# SCH_ZX-WiFi_2025-05-12.net
KiCad netlist of a schematic drawn in EasyEDA
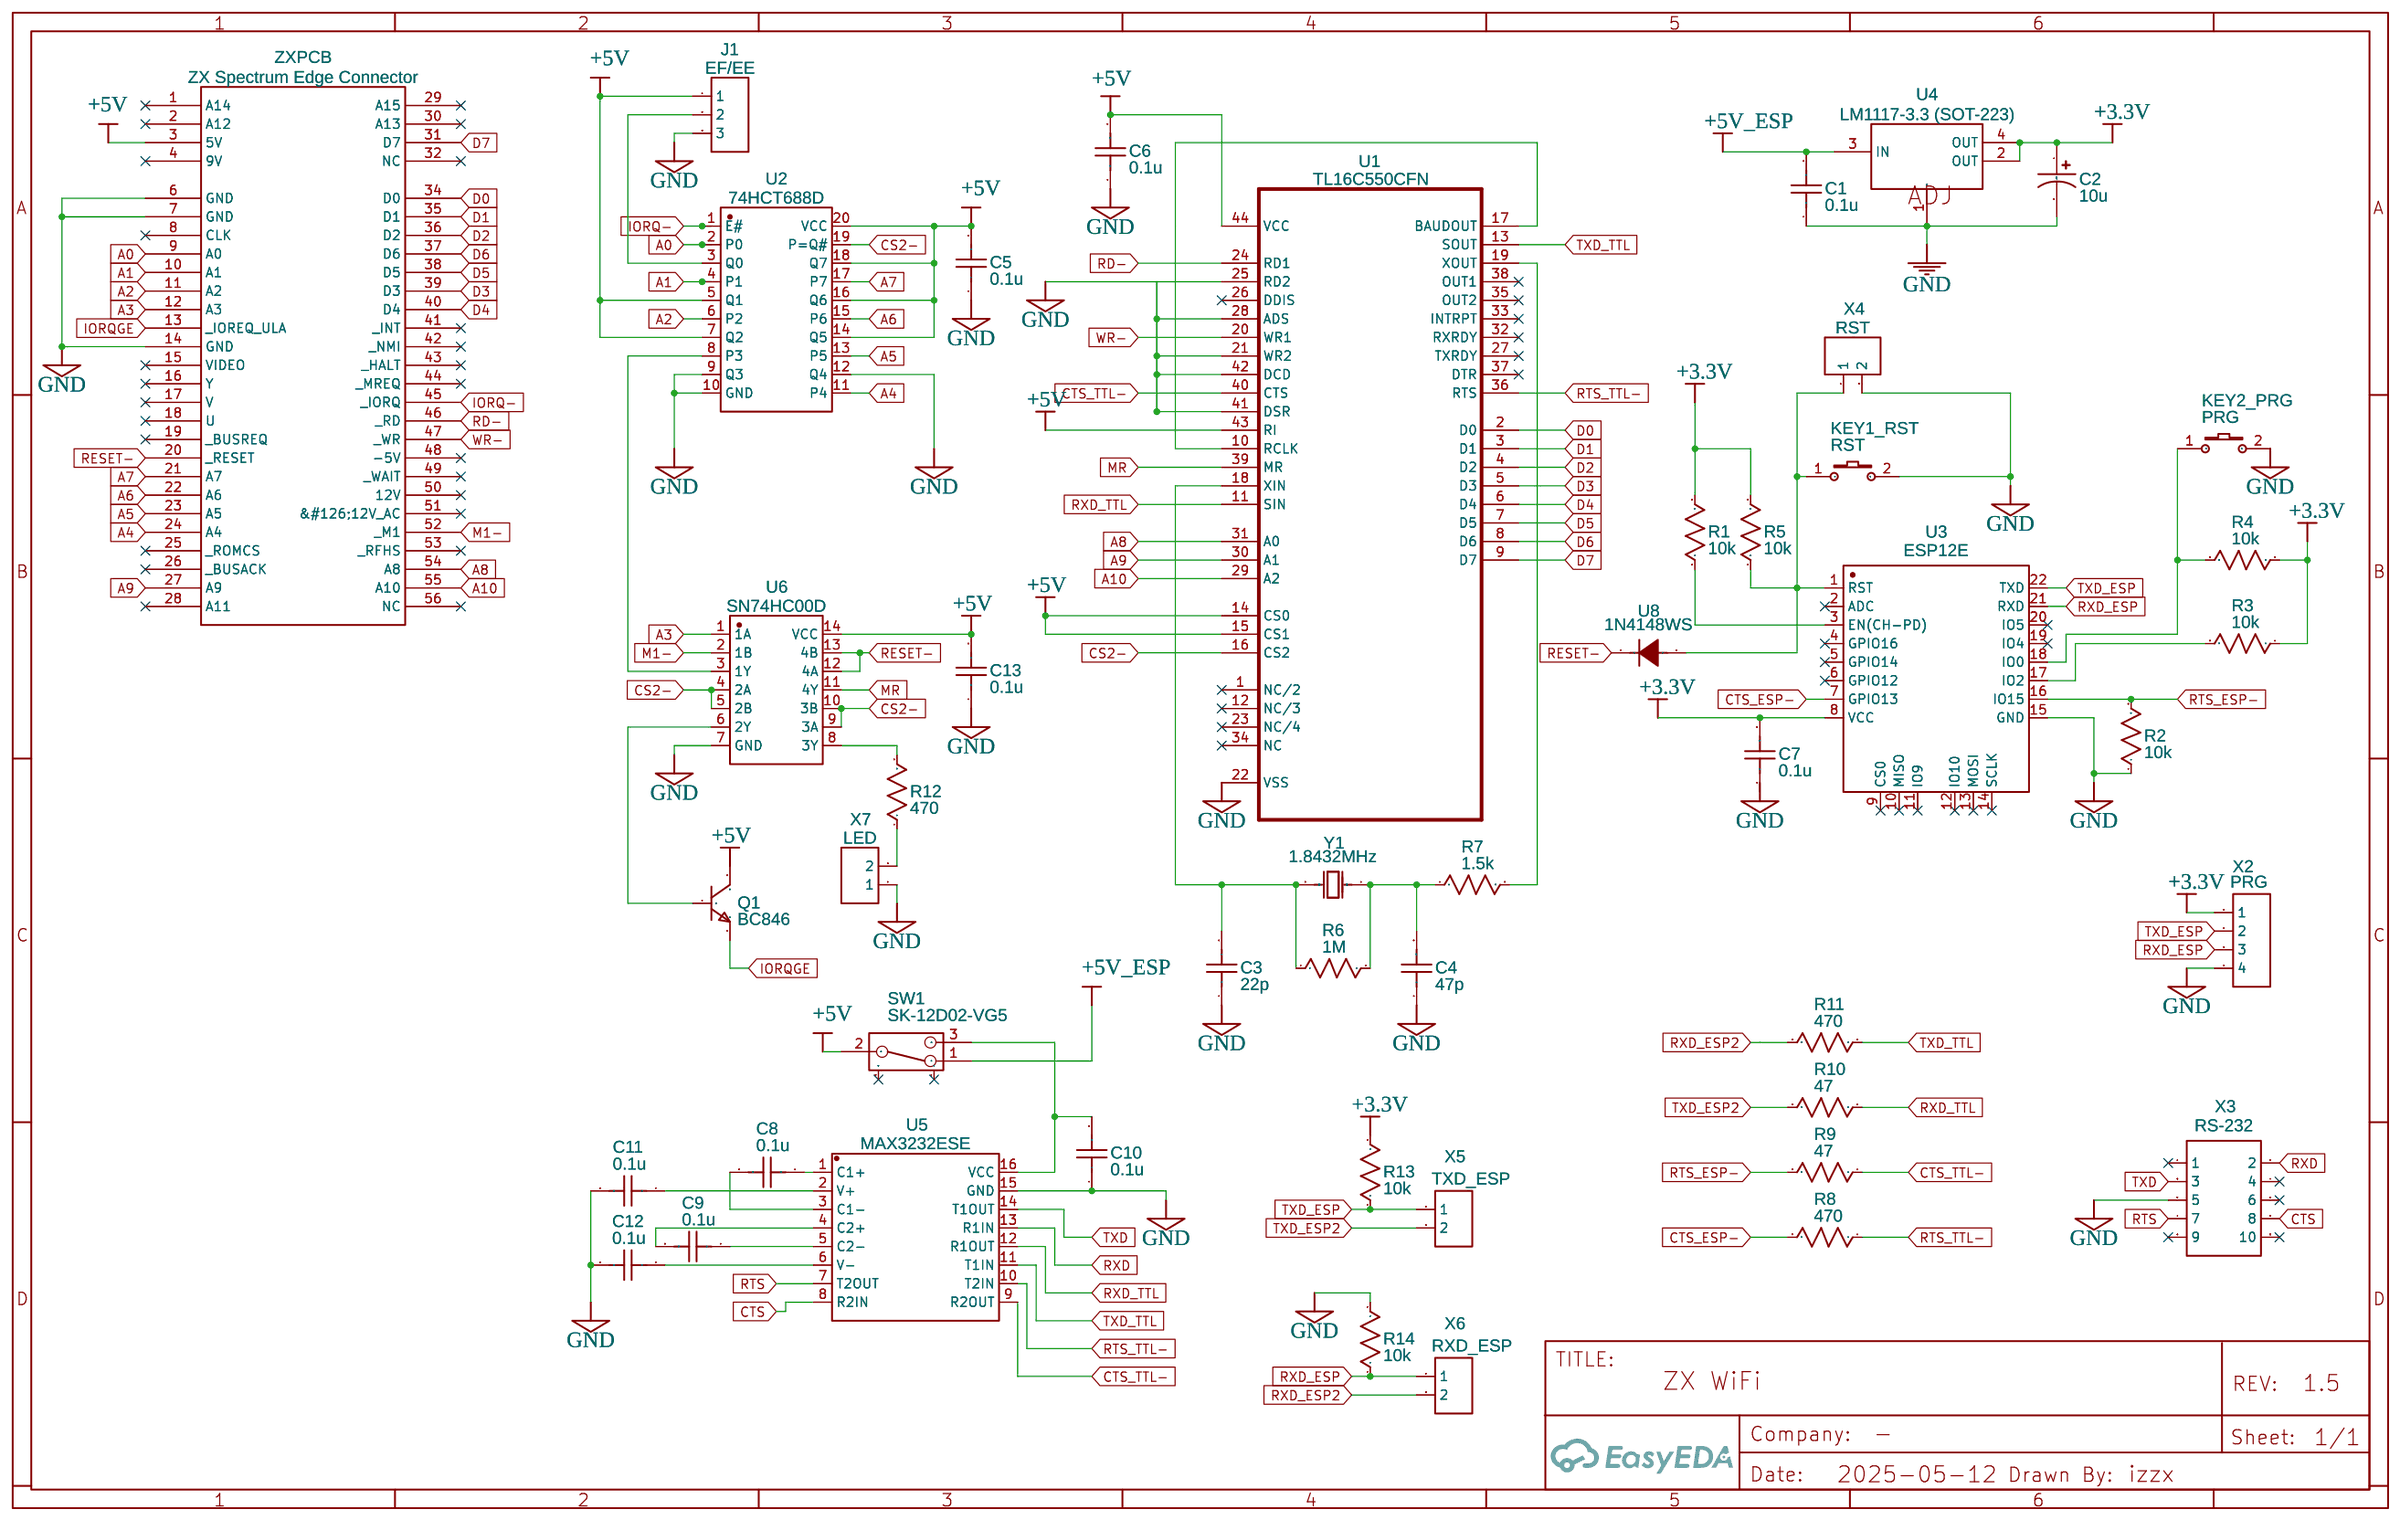
[diagram p0: schematic sheet]

(export (version "E")
  (design (tool "Eeschema 10.0.6"))
  (components
    (comp (ref "C1") (value "0.1u") (libsource (lib "") (part "C_0805_US")))
    (comp (ref "C2") (value "10u") (libsource (lib "") (part "C_Tan_SMD_A_US")))
    (comp (ref "C3") (value "22p") (libsource (lib "") (part "C_0805_US")))
    (comp (ref "C4") (value "47p") (libsource (lib "") (part "C_0805_US")))
    (comp (ref "C5") (value "0.1u") (libsource (lib "") (part "C_0805_US")))
    (comp (ref "C6") (value "0.1u") (libsource (lib "") (part "C_0805_US")))
    (comp (ref "C7") (value "0.1u") (libsource (lib "") (part "C_0805_US")))
    (comp (ref "C8") (value "0.1u") (libsource (lib "") (part "C_0805_US_1")))
    (comp (ref "C9") (value "0.1u") (libsource (lib "") (part "C_0805_US_1")))
    (comp (ref "C10") (value "0.1u") (libsource (lib "") (part "C_0805_US")))
    (comp (ref "C11") (value "0.1u") (libsource (lib "") (part "C_0805_US_1")))
    (comp (ref "C12") (value "0.1u") (libsource (lib "") (part "C_0805_US_1")))
    (comp (ref "C13") (value "0.1u") (libsource (lib "") (part "C_0805_US")))
    (comp (ref "J1") (value "EF/EE") (libsource (lib "") (part "HDR-M-2.54_1x3")))
    (comp (ref "KEY1_RST")
      (value "RST")
      (fields (field (name "Manufacturer Part") "K2-1107ST-A4SW-06"))
      (libsource (lib "") (part "K2-3.6×6.1_SMD"))
    )
    (comp (ref "KEY2_PRG")
      (value "PRG")
      (fields (field (name "Manufacturer Part") "K2-1107ST-A4SW-06"))
      (libsource (lib "") (part "K2-3.6×6.1_SMD_1"))
    )
    (comp (ref "Q1")
      (value "BC846")
      (fields (field (name "Manufacturer Part") "BC846A") (field (name "Manufacturer") "CJ(江苏长电/长晶)"))
      (libsource (lib "") (part "BC846"))
    )
    (comp (ref "R1") (value "10k") (libsource (lib "") (part "R_0805_US_1")))
    (comp (ref "R2") (value "10k") (libsource (lib "") (part "R_0805_US_1")))
    (comp (ref "R3") (value "10k") (libsource (lib "") (part "R_0805_US")))
    (comp (ref "R4") (value "10k") (libsource (lib "") (part "R_0805_US")))
    (comp (ref "R5") (value "10k") (libsource (lib "") (part "R_0805_US_1")))
    (comp (ref "R6") (value "1M") (libsource (lib "") (part "R_0805_US_2")))
    (comp (ref "R7") (value "1.5k") (libsource (lib "") (part "R_0805_US_2")))
    (comp (ref "R8") (value "470") (libsource (lib "") (part "R_0805_US")))
    (comp (ref "R9") (value "47") (libsource (lib "") (part "R_0805_US")))
    (comp (ref "R10") (value "47") (libsource (lib "") (part "R_0805_US")))
    (comp (ref "R11") (value "470") (libsource (lib "") (part "R_0805_US")))
    (comp (ref "R12") (value "470") (libsource (lib "") (part "R_0805_US_1")))
    (comp (ref "R13") (value "10k") (libsource (lib "") (part "R_0805_US_1")))
    (comp (ref "R14") (value "10k") (libsource (lib "") (part "R_0805_US_1")))
    (comp (ref "SW1")
      (value "SK-12D02-VG5")
      (fields (field (name "Manufacturer") "Rectangular Connectors - Contacts"))
      (libsource (lib "") (part "SK-12D02-VG5"))
    )
    (comp (ref "U1") (value "TL16C550CFN") (libsource (lib "") (part "TL16C550CFN")))
    (comp (ref "U2")
      (value "74HCT688D")
      (fields (field (name "Manufacturer") "PHILIPS"))
      (libsource (lib "") (part "74HCT688D"))
    )
    (comp (ref "U3") (value "ESP12E") (libsource (lib "") (part "ESP12E/F")))
    (comp (ref "U4")
      (value "LM1117-3.3 (SOT-223)")
      (fields (field (name "Manufacturer Part") "LM317G-AA3-R") (field (name "Manufacturer") "UTC"))
      (libsource (lib "") (part "LM317(SOT-223)"))
    )
    (comp (ref "U5")
      (value "MAX3232ESE")
      (fields (field (name "Manufacturer") "UMW(友台半导体)"))
      (libsource (lib "") (part "MAX3232ESE"))
    )
    (comp (ref "U6")
      (value "SN74HC00D")
      (fields (field (name "Manufacturer") "TI(德州仪器)"))
      (libsource (lib "") (part "SN74HC00D"))
    )
    (comp (ref "U8")
      (value "1N4148WS")
      (fields (field (name "Manufacturer") "Zhengxin(正芯)"))
      (libsource (lib "") (part "1N4148WS"))
    )
    (comp (ref "X2") (value "PRG") (libsource (lib "") (part "HDR-M-2.54_1x4")))
    (comp (ref "X3") (value "RS-232") (libsource (lib "") (part "HDR-M-2.54_2x5")))
    (comp (ref "X4") (value "RST") (libsource (lib "") (part "HDR-M-2.54_1x2")))
    (comp (ref "X5") (value "TXD_ESP") (libsource (lib "") (part "HDR-F-2.54_1x2")))
    (comp (ref "X6") (value "RXD_ESP") (libsource (lib "") (part "HDR-F-2.54_1x2")))
    (comp (ref "X7") (value "LED") (libsource (lib "") (part "HDR-M-2.54_1x2_1")))
    (comp (ref "Y1")
      (value "1.8432MHz")
      (fields (field (name "Manufacturer Part") "X49UD3579MSD2SC") (field (name "Manufacturer") "ValuePro"))
      (libsource (lib "") (part "X49UD3579MSD2SC"))
    )
    (comp (ref "ZXPCB")
      (value "ZX Spectrum Edge Connector")
      (libsource (lib "") (part "ZX Spectrum Edge Connector"))
    )
  )
  (nets
    (net (code "1") (name "+3.3V") (class "Default")
      (node (ref "C2") (pin "1") (pinfunction "1_1") (pintype "unspecified"))
      (node (ref "C7") (pin "2") (pinfunction "2_2") (pintype "unspecified"))
      (node (ref "R1") (pin "2") (pinfunction "2_2") (pintype "unspecified"))
      (node (ref "R13") (pin "2") (pinfunction "2_2") (pintype "unspecified"))
      (node (ref "R3") (pin "1") (pinfunction "1_1") (pintype "unspecified"))
      (node (ref "R4") (pin "1") (pinfunction "1_1") (pintype "unspecified"))
      (node (ref "R5") (pin "2") (pinfunction "2_2") (pintype "unspecified"))
      (node (ref "U3") (pin "8") (pinfunction "VCC_8") (pintype "unspecified"))
      (node (ref "U4") (pin "2") (pinfunction "OUT_2") (pintype "passive"))
      (node (ref "U4") (pin "4") (pinfunction "OUT_4") (pintype "passive"))
      (node (ref "X2") (pin "1") (pinfunction "1_1") (pintype "unspecified"))
    )
    (net (code "2") (name "+5V") (class "Default")
      (node (ref "C13") (pin "2") (pinfunction "2_2") (pintype "unspecified"))
      (node (ref "C5") (pin "2") (pinfunction "2_2") (pintype "unspecified"))
      (node (ref "C6") (pin "2") (pinfunction "2_2") (pintype "unspecified"))
      (node (ref "J1") (pin "1") (pinfunction "1_1") (pintype "input"))
      (node (ref "Q1") (pin "3") (pinfunction "C_3") (pintype "unspecified"))
      (node (ref "SW1") (pin "2") (pinfunction "2_2") (pintype "unspecified"))
      (node (ref "U1") (pin "14") (pinfunction "CS0_14") (pintype "input"))
      (node (ref "U1") (pin "15") (pinfunction "CS1_15") (pintype "input"))
      (node (ref "U1") (pin "43") (pinfunction "RI_43") (pintype "input"))
      (node (ref "U1") (pin "44") (pinfunction "VCC_44") (pintype "passive"))
      (node (ref "U2") (pin "14") (pinfunction "Q5_14") (pintype "unspecified"))
      (node (ref "U2") (pin "16") (pinfunction "Q6_16") (pintype "unspecified"))
      (node (ref "U2") (pin "18") (pinfunction "Q7_18") (pintype "unspecified"))
      (node (ref "U2") (pin "20") (pinfunction "VCC_20") (pintype "unspecified"))
      (node (ref "U2") (pin "5") (pinfunction "Q1_5") (pintype "unspecified"))
      (node (ref "U2") (pin "7") (pinfunction "Q2_7") (pintype "unspecified"))
      (node (ref "U6") (pin "14") (pinfunction "VCC_14") (pintype "unspecified"))
      (node (ref "ZXPCB") (pin "3") (pinfunction "5V_3") (pintype "unspecified"))
    )
    (net (code "3") (name "+5V_ESP") (class "Default")
      (node (ref "C1") (pin "2") (pinfunction "2_2") (pintype "unspecified"))
      (node (ref "SW1") (pin "1") (pinfunction "1_1") (pintype "unspecified"))
      (node (ref "U4") (pin "3") (pinfunction "IN_3") (pintype "passive"))
    )
    (net (code "4") (name "A0") (class "Default")
      (node (ref "U2") (pin "2") (pinfunction "P0_2") (pintype "unspecified"))
      (node (ref "ZXPCB") (pin "9") (pinfunction "A0_9") (pintype "unspecified"))
    )
    (net (code "5") (name "A1") (class "Default")
      (node (ref "U2") (pin "4") (pinfunction "P1_4") (pintype "unspecified"))
      (node (ref "ZXPCB") (pin "10") (pinfunction "A1_10") (pintype "unspecified"))
    )
    (net (code "6") (name "A2") (class "Default")
      (node (ref "U2") (pin "6") (pinfunction "P2_6") (pintype "unspecified"))
      (node (ref "ZXPCB") (pin "11") (pinfunction "A2_11") (pintype "unspecified"))
    )
    (net (code "7") (name "A3") (class "Default")
      (node (ref "U6") (pin "1") (pinfunction "1A_1") (pintype "unspecified"))
      (node (ref "ZXPCB") (pin "12") (pinfunction "A3_12") (pintype "unspecified"))
    )
    (net (code "8") (name "A4") (class "Default")
      (node (ref "U2") (pin "11") (pinfunction "P4_11") (pintype "unspecified"))
      (node (ref "ZXPCB") (pin "24") (pinfunction "A4_24") (pintype "unspecified"))
    )
    (net (code "9") (name "A5") (class "Default")
      (node (ref "U2") (pin "13") (pinfunction "P5_13") (pintype "unspecified"))
      (node (ref "ZXPCB") (pin "23") (pinfunction "A5_23") (pintype "unspecified"))
    )
    (net (code "10") (name "A6") (class "Default")
      (node (ref "U2") (pin "15") (pinfunction "P6_15") (pintype "unspecified"))
      (node (ref "ZXPCB") (pin "22") (pinfunction "A6_22") (pintype "unspecified"))
    )
    (net (code "11") (name "A7") (class "Default")
      (node (ref "U2") (pin "17") (pinfunction "P7_17") (pintype "unspecified"))
      (node (ref "ZXPCB") (pin "21") (pinfunction "A7_21") (pintype "unspecified"))
    )
    (net (code "12") (name "A8") (class "Default")
      (node (ref "U1") (pin "31") (pinfunction "A0_31") (pintype "input"))
      (node (ref "ZXPCB") (pin "54") (pinfunction "A8_54") (pintype "unspecified"))
    )
    (net (code "13") (name "A9") (class "Default")
      (node (ref "U1") (pin "30") (pinfunction "A1_30") (pintype "input"))
      (node (ref "ZXPCB") (pin "27") (pinfunction "A9_27") (pintype "unspecified"))
    )
    (net (code "14") (name "A10") (class "Default")
      (node (ref "U1") (pin "29") (pinfunction "A2_29") (pintype "input"))
      (node (ref "ZXPCB") (pin "55") (pinfunction "A10_55") (pintype "unspecified"))
    )
    (net (code "15") (name "CS2-") (class "Default")
      (node (ref "U1") (pin "16") (pinfunction "CS2_16") (pintype "input"))
      (node (ref "U2") (pin "19") (pinfunction "P=Q#_19") (pintype "unspecified"))
      (node (ref "U6") (pin "10") (pinfunction "3B_10") (pintype "unspecified"))
      (node (ref "U6") (pin "4") (pinfunction "2A_4") (pintype "unspecified"))
      (node (ref "U6") (pin "5") (pinfunction "2B_5") (pintype "unspecified"))
      (node (ref "U6") (pin "9") (pinfunction "3A_9") (pintype "unspecified"))
    )
    (net (code "16") (name "CTS") (class "Default")
      (node (ref "U5") (pin "8") (pinfunction "R2IN_8") (pintype "unspecified"))
      (node (ref "X3") (pin "8") (pinfunction "8_8") (pintype "unspecified"))
    )
    (net (code "17") (name "CTS_ESP-") (class "Default")
      (node (ref "R8") (pin "2") (pinfunction "2_2") (pintype "unspecified"))
      (node (ref "U3") (pin "7") (pinfunction "GPIO13_7") (pintype "unspecified"))
    )
    (net (code "18") (name "CTS_TTL-") (class "Default")
      (node (ref "R9") (pin "1") (pinfunction "1_1") (pintype "unspecified"))
      (node (ref "U1") (pin "40") (pinfunction "CTS_40") (pintype "input"))
      (node (ref "U5") (pin "9") (pinfunction "R2OUT_9") (pintype "unspecified"))
    )
    (net (code "19") (name "D0") (class "Default")
      (node (ref "U1") (pin "2") (pinfunction "D0_2") (pintype "unspecified"))
      (node (ref "ZXPCB") (pin "34") (pinfunction "D0_34") (pintype "unspecified"))
    )
    (net (code "20") (name "D1") (class "Default")
      (node (ref "U1") (pin "3") (pinfunction "D1_3") (pintype "unspecified"))
      (node (ref "ZXPCB") (pin "35") (pinfunction "D1_35") (pintype "unspecified"))
    )
    (net (code "21") (name "D2") (class "Default")
      (node (ref "U1") (pin "4") (pinfunction "D2_4") (pintype "unspecified"))
      (node (ref "ZXPCB") (pin "36") (pinfunction "D2_36") (pintype "unspecified"))
    )
    (net (code "22") (name "D3") (class "Default")
      (node (ref "U1") (pin "5") (pinfunction "D3_5") (pintype "unspecified"))
      (node (ref "ZXPCB") (pin "39") (pinfunction "D3_39") (pintype "unspecified"))
    )
    (net (code "23") (name "D4") (class "Default")
      (node (ref "U1") (pin "6") (pinfunction "D4_6") (pintype "unspecified"))
      (node (ref "ZXPCB") (pin "40") (pinfunction "D4_40") (pintype "unspecified"))
    )
    (net (code "24") (name "D5") (class "Default")
      (node (ref "U1") (pin "7") (pinfunction "D5_7") (pintype "unspecified"))
      (node (ref "ZXPCB") (pin "38") (pinfunction "D5_38") (pintype "unspecified"))
    )
    (net (code "25") (name "D6") (class "Default")
      (node (ref "U1") (pin "8") (pinfunction "D6_8") (pintype "unspecified"))
      (node (ref "ZXPCB") (pin "37") (pinfunction "D6_37") (pintype "unspecified"))
    )
    (net (code "26") (name "D7") (class "Default")
      (node (ref "U1") (pin "9") (pinfunction "D7_9") (pintype "unspecified"))
      (node (ref "ZXPCB") (pin "31") (pinfunction "D7_31") (pintype "unspecified"))
    )
    (net (code "27") (name "GND") (class "Default")
      (node (ref "C1") (pin "1") (pinfunction "1_1") (pintype "unspecified"))
      (node (ref "C10") (pin "1") (pinfunction "1_1") (pintype "unspecified"))
      (node (ref "C11") (pin "2") (pinfunction "2_2") (pintype "unspecified"))
      (node (ref "C12") (pin "2") (pinfunction "2_2") (pintype "unspecified"))
      (node (ref "C13") (pin "1") (pinfunction "1_1") (pintype "unspecified"))
      (node (ref "C2") (pin "2") (pinfunction "2_2") (pintype "unspecified"))
      (node (ref "C3") (pin "1") (pinfunction "1_1") (pintype "unspecified"))
      (node (ref "C4") (pin "1") (pinfunction "1_1") (pintype "unspecified"))
      (node (ref "C5") (pin "1") (pinfunction "1_1") (pintype "unspecified"))
      (node (ref "C6") (pin "1") (pinfunction "1_1") (pintype "unspecified"))
      (node (ref "C7") (pin "1") (pinfunction "1_1") (pintype "unspecified"))
      (node (ref "J1") (pin "3") (pinfunction "3_3") (pintype "input"))
      (node (ref "KEY1_RST") (pin "2") (pinfunction "2_2") (pintype "unspecified"))
      (node (ref "KEY2_PRG") (pin "2") (pinfunction "2_2") (pintype "unspecified"))
      (node (ref "R14") (pin "2") (pinfunction "2_2") (pintype "unspecified"))
      (node (ref "R2") (pin "1") (pinfunction "1_1") (pintype "unspecified"))
      (node (ref "U1") (pin "21") (pinfunction "WR2_21") (pintype "input"))
      (node (ref "U1") (pin "22") (pinfunction "VSS_22") (pintype "passive"))
      (node (ref "U1") (pin "25") (pinfunction "RD2_25") (pintype "input"))
      (node (ref "U1") (pin "28") (pinfunction "ADS_28") (pintype "input"))
      (node (ref "U1") (pin "41") (pinfunction "DSR_41") (pintype "input"))
      (node (ref "U1") (pin "42") (pinfunction "DCD_42") (pintype "input"))
      (node (ref "U2") (pin "10") (pinfunction "GND_10") (pintype "unspecified"))
      (node (ref "U2") (pin "12") (pinfunction "Q4_12") (pintype "unspecified"))
      (node (ref "U2") (pin "9") (pinfunction "Q3_9") (pintype "unspecified"))
      (node (ref "U3") (pin "15") (pinfunction "GND_15") (pintype "unspecified"))
      (node (ref "U4") (pin "1") (pinfunction "ADJ_1") (pintype "passive"))
      (node (ref "U5") (pin "15") (pinfunction "GND_15") (pintype "unspecified"))
      (node (ref "U6") (pin "7") (pinfunction "GND_7") (pintype "unspecified"))
      (node (ref "X2") (pin "4") (pinfunction "4_4") (pintype "unspecified"))
      (node (ref "X3") (pin "5") (pinfunction "5_5") (pintype "unspecified"))
      (node (ref "X4") (pin "2") (pinfunction "2_2") (pintype "unspecified"))
      (node (ref "X7") (pin "1") (pinfunction "1_1") (pintype "unspecified"))
      (node (ref "ZXPCB") (pin "14") (pinfunction "GND_14") (pintype "unspecified"))
      (node (ref "ZXPCB") (pin "6") (pinfunction "GND_6") (pintype "unspecified"))
      (node (ref "ZXPCB") (pin "7") (pinfunction "GND_7") (pintype "unspecified"))
    )
    (net (code "28") (name "IORQ-") (class "Default")
      (node (ref "U2") (pin "1") (pinfunction "E#_1") (pintype "unspecified"))
      (node (ref "ZXPCB") (pin "45") (pinfunction "_IORQ_45") (pintype "unspecified"))
    )
    (net (code "29") (name "IORQGE") (class "Default")
      (node (ref "Q1") (pin "2") (pinfunction "E_2") (pintype "unspecified"))
      (node (ref "ZXPCB") (pin "13") (pinfunction "_IOREQ_ULA_13") (pintype "unspecified"))
    )
    (net (code "30") (name "M1-") (class "Default")
      (node (ref "U6") (pin "2") (pinfunction "1B_2") (pintype "unspecified"))
      (node (ref "ZXPCB") (pin "52") (pinfunction "_M1_52") (pintype "unspecified"))
    )
    (net (code "31") (name "MR") (class "Default")
      (node (ref "U1") (pin "39") (pinfunction "MR_39") (pintype "input"))
      (node (ref "U6") (pin "11") (pinfunction "4Y_11") (pintype "unspecified"))
    )
    (net (code "32") (name "Net-(Q1-B)") (class "Default")
      (node (ref "Q1") (pin "1") (pinfunction "B_1") (pintype "unspecified"))
      (node (ref "U6") (pin "6") (pinfunction "2Y_6") (pintype "unspecified"))
    )
    (net (code "33") (name "Net-(R12-Pad1)") (class "Default")
      (node (ref "R12") (pin "1") (pinfunction "1_1") (pintype "unspecified"))
      (node (ref "X7") (pin "2") (pinfunction "2_2") (pintype "unspecified"))
    )
    (net (code "34") (name "Net-(U1-BAUDOUT)") (class "Default")
      (node (ref "U1") (pin "10") (pinfunction "RCLK_10") (pintype "input"))
      (node (ref "U1") (pin "17") (pinfunction "BAUDOUT_17") (pintype "output"))
    )
    (net (code "35") (name "Net-(U1-XIN)") (class "Default")
      (node (ref "C3") (pin "2") (pinfunction "2_2") (pintype "unspecified"))
      (node (ref "R6") (pin "1") (pinfunction "1_1") (pintype "unspecified"))
      (node (ref "U1") (pin "18") (pinfunction "XIN_18") (pintype "input"))
      (node (ref "Y1") (pin "2") (pinfunction "OSC2_2") (pintype "input"))
    )
    (net (code "36") (name "Net-(U1-XOUT)") (class "Default")
      (node (ref "R7") (pin "2") (pinfunction "2_2") (pintype "unspecified"))
      (node (ref "U1") (pin "19") (pinfunction "XOUT_19") (pintype "output"))
    )
    (net (code "37") (name "Net-(U2-P3)") (class "Default")
      (node (ref "U2") (pin "8") (pinfunction "P3_8") (pintype "unspecified"))
      (node (ref "U6") (pin "3") (pinfunction "1Y_3") (pintype "unspecified"))
    )
    (net (code "38") (name "Net-(U2-Q0)") (class "Default")
      (node (ref "J1") (pin "2") (pinfunction "2_2") (pintype "input"))
      (node (ref "U2") (pin "3") (pinfunction "Q0_3") (pintype "unspecified"))
    )
    (net (code "39") (name "Net-(U3-EN(CH-PD))") (class "Default")
      (node (ref "R1") (pin "1") (pinfunction "1_1") (pintype "unspecified"))
      (node (ref "U3") (pin "3") (pinfunction "EN(CH-PD)_3") (pintype "unspecified"))
    )
    (net (code "40") (name "Net-(U3-IO0)") (class "Default")
      (node (ref "KEY2_PRG") (pin "1") (pinfunction "1_1") (pintype "unspecified"))
      (node (ref "R4") (pin "2") (pinfunction "2_2") (pintype "unspecified"))
      (node (ref "U3") (pin "18") (pinfunction "IO0_18") (pintype "unspecified"))
    )
    (net (code "41") (name "Net-(U3-IO2)") (class "Default")
      (node (ref "R3") (pin "2") (pinfunction "2_2") (pintype "unspecified"))
      (node (ref "U3") (pin "17") (pinfunction "IO2_17") (pintype "unspecified"))
    )
    (net (code "42") (name "Net-(U3-RST)") (class "Default")
      (node (ref "KEY1_RST") (pin "1") (pinfunction "1_1") (pintype "unspecified"))
      (node (ref "R5") (pin "1") (pinfunction "1_1") (pintype "unspecified"))
      (node (ref "U3") (pin "1") (pinfunction "RST_1") (pintype "unspecified"))
      (node (ref "U8") (pin "2") (pinfunction "A_2") (pintype "unspecified"))
      (node (ref "X4") (pin "1") (pinfunction "1_1") (pintype "unspecified"))
    )
    (net (code "43") (name "Net-(U5-C1+)") (class "Default")
      (node (ref "C8") (pin "1") (pinfunction "1_1") (pintype "unspecified"))
      (node (ref "U5") (pin "1") (pinfunction "C1+_1") (pintype "unspecified"))
    )
    (net (code "44") (name "Net-(U5-C1-)") (class "Default")
      (node (ref "C8") (pin "2") (pinfunction "2_2") (pintype "unspecified"))
      (node (ref "U5") (pin "3") (pinfunction "C1-_3") (pintype "unspecified"))
    )
    (net (code "45") (name "Net-(U5-C2+)") (class "Default")
      (node (ref "C9") (pin "2") (pinfunction "2_2") (pintype "unspecified"))
      (node (ref "U5") (pin "4") (pinfunction "C2+_4") (pintype "unspecified"))
    )
    (net (code "46") (name "Net-(U5-C2-)") (class "Default")
      (node (ref "C9") (pin "1") (pinfunction "1_1") (pintype "unspecified"))
      (node (ref "U5") (pin "5") (pinfunction "C2-_5") (pintype "unspecified"))
    )
    (net (code "47") (name "Net-(U5-V+)") (class "Default")
      (node (ref "C11") (pin "1") (pinfunction "1_1") (pintype "unspecified"))
      (node (ref "U5") (pin "2") (pinfunction "V+_2") (pintype "unspecified"))
    )
    (net (code "48") (name "Net-(U5-V-)") (class "Default")
      (node (ref "C12") (pin "1") (pinfunction "1_1") (pintype "unspecified"))
      (node (ref "U5") (pin "6") (pinfunction "V-_6") (pintype "unspecified"))
    )
    (net (code "49") (name "Net-(U5-VCC)") (class "Default")
      (node (ref "C10") (pin "2") (pinfunction "2_2") (pintype "unspecified"))
      (node (ref "SW1") (pin "3") (pinfunction "3_3") (pintype "unspecified"))
      (node (ref "U5") (pin "16") (pinfunction "VCC_16") (pintype "unspecified"))
    )
    (net (code "50") (name "Net-(U6-3Y)") (class "Default")
      (node (ref "R12") (pin "2") (pinfunction "2_2") (pintype "unspecified"))
      (node (ref "U6") (pin "8") (pinfunction "3Y_8") (pintype "unspecified"))
    )
    (net (code "51") (name "Net-(Y1-OSC1)") (class "Default")
      (node (ref "C4") (pin "2") (pinfunction "2_2") (pintype "unspecified"))
      (node (ref "R6") (pin "2") (pinfunction "2_2") (pintype "unspecified"))
      (node (ref "R7") (pin "1") (pinfunction "1_1") (pintype "unspecified"))
      (node (ref "Y1") (pin "1") (pinfunction "OSC1_1") (pintype "input"))
    )
    (net (code "52") (name "RD-") (class "Default")
      (node (ref "U1") (pin "24") (pinfunction "RD1_24") (pintype "input"))
      (node (ref "ZXPCB") (pin "46") (pinfunction "_RD_46") (pintype "unspecified"))
    )
    (net (code "53") (name "RESET-") (class "Default")
      (node (ref "U6") (pin "12") (pinfunction "4A_12") (pintype "unspecified"))
      (node (ref "U6") (pin "13") (pinfunction "4B_13") (pintype "unspecified"))
      (node (ref "U8") (pin "1") (pinfunction "K_1") (pintype "unspecified"))
      (node (ref "ZXPCB") (pin "20") (pinfunction "_RESET_20") (pintype "unspecified"))
    )
    (net (code "54") (name "RTS") (class "Default")
      (node (ref "U5") (pin "7") (pinfunction "T2OUT_7") (pintype "unspecified"))
      (node (ref "X3") (pin "7") (pinfunction "7_7") (pintype "unspecified"))
    )
    (net (code "55") (name "RTS_ESP-") (class "Default")
      (node (ref "R2") (pin "2") (pinfunction "2_2") (pintype "unspecified"))
      (node (ref "R9") (pin "2") (pinfunction "2_2") (pintype "unspecified"))
      (node (ref "U3") (pin "16") (pinfunction "IO15_16") (pintype "unspecified"))
    )
    (net (code "56") (name "RTS_TTL-") (class "Default")
      (node (ref "R8") (pin "1") (pinfunction "1_1") (pintype "unspecified"))
      (node (ref "U1") (pin "36") (pinfunction "RTS_36") (pintype "output"))
      (node (ref "U5") (pin "10") (pinfunction "T2IN_10") (pintype "unspecified"))
    )
    (net (code "57") (name "RXD") (class "Default")
      (node (ref "U5") (pin "13") (pinfunction "R1IN_13") (pintype "unspecified"))
      (node (ref "X3") (pin "2") (pinfunction "2_2") (pintype "unspecified"))
    )
    (net (code "58") (name "RXD_ESP") (class "Default")
      (node (ref "R14") (pin "1") (pinfunction "1_1") (pintype "unspecified"))
      (node (ref "U3") (pin "21") (pinfunction "RXD_21") (pintype "unspecified"))
      (node (ref "X2") (pin "3") (pinfunction "3_3") (pintype "unspecified"))
      (node (ref "X6") (pin "1") (pinfunction "1_1") (pintype "input"))
    )
    (net (code "59") (name "RXD_ESP2") (class "Default")
      (node (ref "R11") (pin "2") (pinfunction "2_2") (pintype "unspecified"))
      (node (ref "X6") (pin "2") (pinfunction "2_2") (pintype "input"))
    )
    (net (code "60") (name "RXD_TTL") (class "Default")
      (node (ref "R10") (pin "1") (pinfunction "1_1") (pintype "unspecified"))
      (node (ref "U1") (pin "11") (pinfunction "SIN_11") (pintype "input"))
      (node (ref "U5") (pin "12") (pinfunction "R1OUT_12") (pintype "unspecified"))
    )
    (net (code "61") (name "TXD") (class "Default")
      (node (ref "U5") (pin "14") (pinfunction "T1OUT_14") (pintype "unspecified"))
      (node (ref "X3") (pin "3") (pinfunction "3_3") (pintype "unspecified"))
    )
    (net (code "62") (name "TXD_ESP") (class "Default")
      (node (ref "R13") (pin "1") (pinfunction "1_1") (pintype "unspecified"))
      (node (ref "U3") (pin "22") (pinfunction "TXD_22") (pintype "unspecified"))
      (node (ref "X2") (pin "2") (pinfunction "2_2") (pintype "unspecified"))
      (node (ref "X5") (pin "1") (pinfunction "1_1") (pintype "input"))
    )
    (net (code "63") (name "TXD_ESP2") (class "Default")
      (node (ref "R10") (pin "2") (pinfunction "2_2") (pintype "unspecified"))
      (node (ref "X5") (pin "2") (pinfunction "2_2") (pintype "input"))
    )
    (net (code "64") (name "TXD_TTL") (class "Default")
      (node (ref "R11") (pin "1") (pinfunction "1_1") (pintype "unspecified"))
      (node (ref "U1") (pin "13") (pinfunction "SOUT_13") (pintype "output"))
      (node (ref "U5") (pin "11") (pinfunction "T1IN_11") (pintype "unspecified"))
    )
    (net (code "65") (name "WR-") (class "Default")
      (node (ref "U1") (pin "20") (pinfunction "WR1_20") (pintype "input"))
      (node (ref "ZXPCB") (pin "47") (pinfunction "_WR_47") (pintype "unspecified"))
    )
    (net (code "66") (name "unconnected-(SW1-Pad4)") (class "Default")
      (node (ref "SW1") (pin "4") (pinfunction "4_4") (pintype "unspecified+no_connect"))
    )
    (net (code "67") (name "unconnected-(SW1-Pad5)") (class "Default")
      (node (ref "SW1") (pin "5") (pinfunction "5_5") (pintype "unspecified+no_connect"))
    )
    (net (code "68") (name "unconnected-(U1-DDIS-Pad26)") (class "Default")
      (node (ref "U1") (pin "26") (pinfunction "DDIS_26") (pintype "input+no_connect"))
    )
    (net (code "69") (name "unconnected-(U1-DTR-Pad37)") (class "Default")
      (node (ref "U1") (pin "37") (pinfunction "DTR_37") (pintype "output+no_connect"))
    )
    (net (code "70") (name "unconnected-(U1-INTRPT-Pad33)") (class "Default")
      (node (ref "U1") (pin "33") (pinfunction "INTRPT_33") (pintype "output+no_connect"))
    )
    (net (code "71") (name "unconnected-(U1-NC-Pad34)") (class "Default")
      (node (ref "U1") (pin "34") (pinfunction "NC_34") (pintype "unspecified+no_connect"))
    )
    (net (code "72") (name "unconnected-(U1-NC{slash}2-Pad1)") (class "Default")
      (node (ref "U1") (pin "1") (pinfunction "NC/2_1") (pintype "unspecified+no_connect"))
    )
    (net (code "73") (name "unconnected-(U1-NC{slash}3-Pad12)") (class "Default")
      (node (ref "U1") (pin "12") (pinfunction "NC/3_12") (pintype "unspecified+no_connect"))
    )
    (net (code "74") (name "unconnected-(U1-NC{slash}4-Pad23)") (class "Default")
      (node (ref "U1") (pin "23") (pinfunction "NC/4_23") (pintype "unspecified+no_connect"))
    )
    (net (code "75") (name "unconnected-(U1-OUT1-Pad38)") (class "Default")
      (node (ref "U1") (pin "38") (pinfunction "OUT1_38") (pintype "output+no_connect"))
    )
    (net (code "76") (name "unconnected-(U1-OUT2-Pad35)") (class "Default")
      (node (ref "U1") (pin "35") (pinfunction "OUT2_35") (pintype "output+no_connect"))
    )
    (net (code "77") (name "unconnected-(U1-RXRDY-Pad32)") (class "Default")
      (node (ref "U1") (pin "32") (pinfunction "RXRDY_32") (pintype "output+no_connect"))
    )
    (net (code "78") (name "unconnected-(U1-TXRDY-Pad27)") (class "Default")
      (node (ref "U1") (pin "27") (pinfunction "TXRDY_27") (pintype "output+no_connect"))
    )
    (net (code "79") (name "unconnected-(U3-ADC-Pad2)") (class "Default")
      (node (ref "U3") (pin "2") (pinfunction "ADC_2") (pintype "unspecified+no_connect"))
    )
    (net (code "80") (name "unconnected-(U3-CS0-Pad9)") (class "Default")
      (node (ref "U3") (pin "9") (pinfunction "CS0_9") (pintype "unspecified+no_connect"))
    )
    (net (code "81") (name "unconnected-(U3-GPIO12-Pad6)") (class "Default")
      (node (ref "U3") (pin "6") (pinfunction "GPIO12_6") (pintype "unspecified+no_connect"))
    )
    (net (code "82") (name "unconnected-(U3-GPIO14-Pad5)") (class "Default")
      (node (ref "U3") (pin "5") (pinfunction "GPIO14_5") (pintype "unspecified+no_connect"))
    )
    (net (code "83") (name "unconnected-(U3-GPIO16-Pad4)") (class "Default")
      (node (ref "U3") (pin "4") (pinfunction "GPIO16_4") (pintype "unspecified+no_connect"))
    )
    (net (code "84") (name "unconnected-(U3-IO4-Pad19)") (class "Default")
      (node (ref "U3") (pin "19") (pinfunction "IO4_19") (pintype "unspecified+no_connect"))
    )
    (net (code "85") (name "unconnected-(U3-IO5-Pad20)") (class "Default")
      (node (ref "U3") (pin "20") (pinfunction "IO5_20") (pintype "unspecified+no_connect"))
    )
    (net (code "86") (name "unconnected-(U3-IO9-Pad11)") (class "Default")
      (node (ref "U3") (pin "11") (pinfunction "IO9_11") (pintype "unspecified+no_connect"))
    )
    (net (code "87") (name "unconnected-(U3-IO10-Pad12)") (class "Default")
      (node (ref "U3") (pin "12") (pinfunction "IO10_12") (pintype "unspecified+no_connect"))
    )
    (net (code "88") (name "unconnected-(U3-MISO-Pad10)") (class "Default")
      (node (ref "U3") (pin "10") (pinfunction "MISO_10") (pintype "unspecified+no_connect"))
    )
    (net (code "89") (name "unconnected-(U3-MOSI-Pad13)") (class "Default")
      (node (ref "U3") (pin "13") (pinfunction "MOSI_13") (pintype "unspecified+no_connect"))
    )
    (net (code "90") (name "unconnected-(U3-SCLK-Pad14)") (class "Default")
      (node (ref "U3") (pin "14") (pinfunction "SCLK_14") (pintype "unspecified+no_connect"))
    )
    (net (code "91") (name "unconnected-(X3-Pad1)") (class "Default")
      (node (ref "X3") (pin "1") (pinfunction "1_1") (pintype "unspecified+no_connect"))
    )
    (net (code "92") (name "unconnected-(X3-Pad4)") (class "Default")
      (node (ref "X3") (pin "4") (pinfunction "4_4") (pintype "unspecified+no_connect"))
    )
    (net (code "93") (name "unconnected-(X3-Pad6)") (class "Default")
      (node (ref "X3") (pin "6") (pinfunction "6_6") (pintype "unspecified+no_connect"))
    )
    (net (code "94") (name "unconnected-(X3-Pad9)") (class "Default")
      (node (ref "X3") (pin "9") (pinfunction "9_9") (pintype "unspecified+no_connect"))
    )
    (net (code "95") (name "unconnected-(X3-Pad10)") (class "Default")
      (node (ref "X3") (pin "10") (pinfunction "10_10") (pintype "unspecified+no_connect"))
    )
    (net (code "96") (name "unconnected-(ZXPCB-&#126;12V_AC-Pad51)") (class "Default")
      (node (ref "ZXPCB") (pin "51") (pinfunction "&#126;12V_AC_51") (pintype "unspecified+no_connect"))
    )
    (net (code "97") (name "unconnected-(ZXPCB--5V-Pad48)") (class "Default")
      (node (ref "ZXPCB") (pin "48") (pinfunction "-5V_48") (pintype "unspecified+no_connect"))
    )
    (net (code "98") (name "unconnected-(ZXPCB-9V-Pad4)") (class "Default")
      (node (ref "ZXPCB") (pin "4") (pinfunction "9V_4") (pintype "unspecified+no_connect"))
    )
    (net (code "99") (name "unconnected-(ZXPCB-12V-Pad50)") (class "Default")
      (node (ref "ZXPCB") (pin "50") (pinfunction "12V_50") (pintype "unspecified+no_connect"))
    )
    (net (code "100") (name "unconnected-(ZXPCB-A11-Pad28)") (class "Default")
      (node (ref "ZXPCB") (pin "28") (pinfunction "A11_28") (pintype "unspecified+no_connect"))
    )
    (net (code "101") (name "unconnected-(ZXPCB-A12-Pad2)") (class "Default")
      (node (ref "ZXPCB") (pin "2") (pinfunction "A12_2") (pintype "unspecified+no_connect"))
    )
    (net (code "102") (name "unconnected-(ZXPCB-A13-Pad30)") (class "Default")
      (node (ref "ZXPCB") (pin "30") (pinfunction "A13_30") (pintype "unspecified+no_connect"))
    )
    (net (code "103") (name "unconnected-(ZXPCB-A14-Pad1)") (class "Default")
      (node (ref "ZXPCB") (pin "1") (pinfunction "A14_1") (pintype "unspecified+no_connect"))
    )
    (net (code "104") (name "unconnected-(ZXPCB-A15-Pad29)") (class "Default")
      (node (ref "ZXPCB") (pin "29") (pinfunction "A15_29") (pintype "unspecified+no_connect"))
    )
    (net (code "105") (name "unconnected-(ZXPCB-CLK-Pad8)") (class "Default")
      (node (ref "ZXPCB") (pin "8") (pinfunction "CLK_8") (pintype "unspecified+no_connect"))
    )
    (net (code "106") (name "unconnected-(ZXPCB-NC-Pad32)") (class "Default")
      (node (ref "ZXPCB") (pin "32") (pinfunction "NC_32") (pintype "unspecified+no_connect"))
    )
    (net (code "107") (name "unconnected-(ZXPCB-NC-Pad56)") (class "Default")
      (node (ref "ZXPCB") (pin "56") (pinfunction "NC_56") (pintype "unspecified+no_connect"))
    )
    (net (code "108") (name "unconnected-(ZXPCB-U-Pad18)") (class "Default")
      (node (ref "ZXPCB") (pin "18") (pinfunction "U_18") (pintype "unspecified+no_connect"))
    )
    (net (code "109") (name "unconnected-(ZXPCB-V-Pad17)") (class "Default")
      (node (ref "ZXPCB") (pin "17") (pinfunction "V_17") (pintype "unspecified+no_connect"))
    )
    (net (code "110") (name "unconnected-(ZXPCB-VIDEO-Pad15)") (class "Default")
      (node (ref "ZXPCB") (pin "15") (pinfunction "VIDEO_15") (pintype "unspecified+no_connect"))
    )
    (net (code "111") (name "unconnected-(ZXPCB-Y-Pad16)") (class "Default")
      (node (ref "ZXPCB") (pin "16") (pinfunction "Y_16") (pintype "unspecified+no_connect"))
    )
    (net (code "112") (name "unconnected-(ZXPCB-_BUSACK-Pad26)") (class "Default")
      (node (ref "ZXPCB") (pin "26") (pinfunction "_BUSACK_26") (pintype "unspecified+no_connect"))
    )
    (net (code "113") (name "unconnected-(ZXPCB-_BUSREQ-Pad19)") (class "Default")
      (node (ref "ZXPCB") (pin "19") (pinfunction "_BUSREQ_19") (pintype "unspecified+no_connect"))
    )
    (net (code "114") (name "unconnected-(ZXPCB-_HALT-Pad43)") (class "Default")
      (node (ref "ZXPCB") (pin "43") (pinfunction "_HALT_43") (pintype "unspecified+no_connect"))
    )
    (net (code "115") (name "unconnected-(ZXPCB-_INT-Pad41)") (class "Default")
      (node (ref "ZXPCB") (pin "41") (pinfunction "_INT_41") (pintype "unspecified+no_connect"))
    )
    (net (code "116") (name "unconnected-(ZXPCB-_MREQ-Pad44)") (class "Default")
      (node (ref "ZXPCB") (pin "44") (pinfunction "_MREQ_44") (pintype "unspecified+no_connect"))
    )
    (net (code "117") (name "unconnected-(ZXPCB-_NMI-Pad42)") (class "Default")
      (node (ref "ZXPCB") (pin "42") (pinfunction "_NMI_42") (pintype "unspecified+no_connect"))
    )
    (net (code "118") (name "unconnected-(ZXPCB-_RFHS-Pad53)") (class "Default")
      (node (ref "ZXPCB") (pin "53") (pinfunction "_RFHS_53") (pintype "unspecified+no_connect"))
    )
    (net (code "119") (name "unconnected-(ZXPCB-_ROMCS-Pad25)") (class "Default")
      (node (ref "ZXPCB") (pin "25") (pinfunction "_ROMCS_25") (pintype "unspecified+no_connect"))
    )
    (net (code "120") (name "unconnected-(ZXPCB-_WAIT-Pad49)") (class "Default")
      (node (ref "ZXPCB") (pin "49") (pinfunction "_WAIT_49") (pintype "unspecified+no_connect"))
    )
  )
)
